# amp_soha_v2.net
KiCad netlist of a schematic drawn in EAGLE
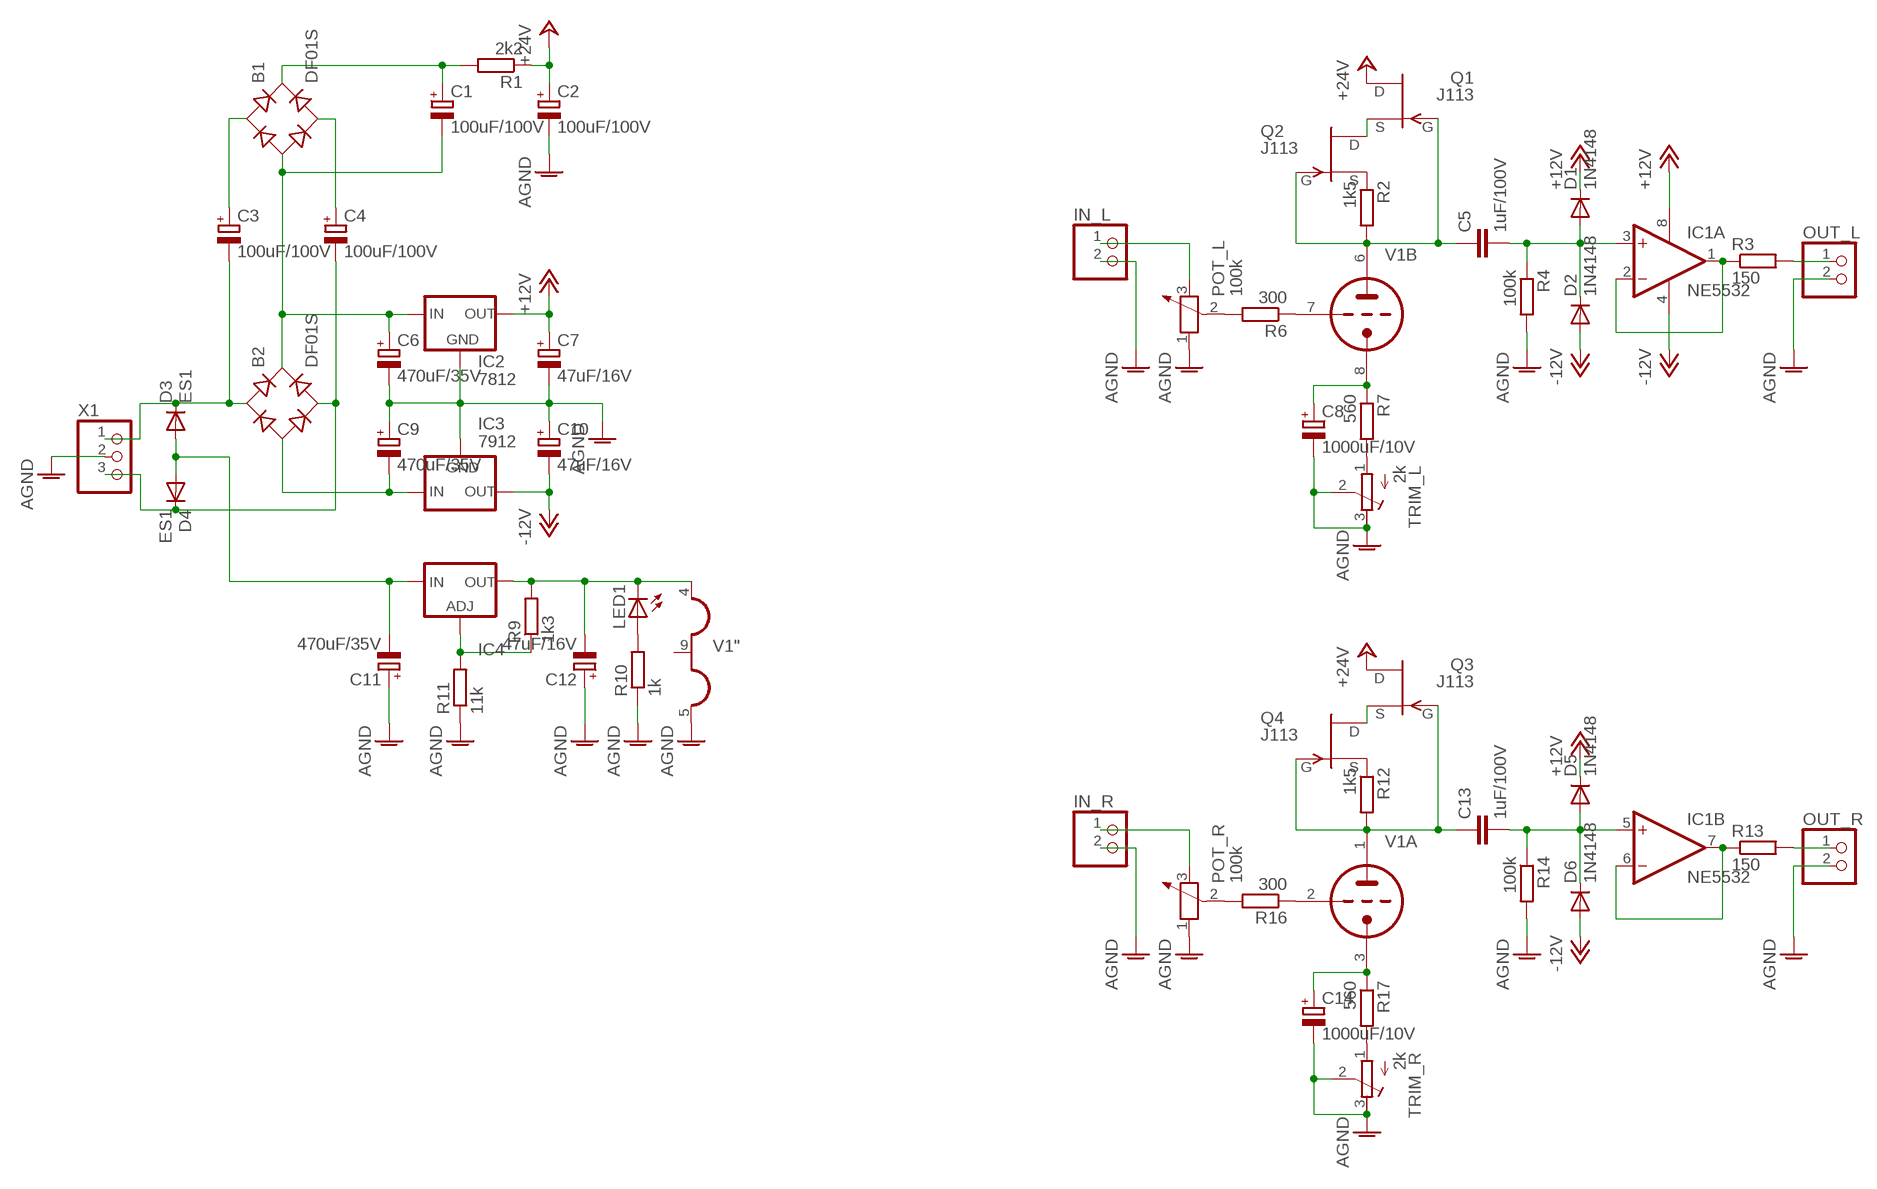
[diagram p0: schematic, sheet 1]

(export (version "E")
  (design (tool "Eeschema 10.0.6"))
  (components
    (comp (ref "B1")
      (value "DF01S")
      (footprint "eagle-import:DFS")
      (libsource (lib "eagle-import") (part "DFS01"))
    )
    (comp (ref "B2")
      (value "DF01S")
      (footprint "eagle-import:DFS")
      (libsource (lib "eagle-import") (part "DFS01"))
    )
    (comp (ref "C1")
      (value "100uF/100V")
      (footprint "eagle-import:E5-10,5")
      (libsource (lib "eagle-import") (part "CPOL-EUE5-10,5"))
    )
    (comp (ref "C2")
      (value "100uF/100V")
      (footprint "eagle-import:E5-10,5")
      (libsource (lib "eagle-import") (part "CPOL-EUE5-10,5"))
    )
    (comp (ref "C3")
      (value "100uF/100V")
      (footprint "eagle-import:E5-10,5")
      (libsource (lib "eagle-import") (part "CPOL-EUE5-10,5"))
    )
    (comp (ref "C4")
      (value "100uF/100V")
      (footprint "eagle-import:E5-10,5")
      (libsource (lib "eagle-import") (part "CPOL-EUE5-10,5"))
    )
    (comp (ref "C5")
      (value "1uF/100V")
      (footprint "eagle-import:C075-052X106")
      (libsource (lib "eagle-import") (part "C-EU075-052X106"))
    )
    (comp (ref "C6")
      (value "470uF/35V")
      (footprint "eagle-import:E5-10,5")
      (libsource (lib "eagle-import") (part "CPOL-EUE5-10,5"))
    )
    (comp (ref "C7")
      (value "47uF/16V")
      (footprint "eagle-import:E2,5-6")
      (libsource (lib "eagle-import") (part "CPOL-EUE2.5-6"))
    )
    (comp (ref "C8")
      (value "1000uF/10V")
      (footprint "eagle-import:E5-10,5")
      (libsource (lib "eagle-import") (part "CPOL-EUE5-10,5"))
    )
    (comp (ref "C9")
      (value "470uF/35V")
      (footprint "eagle-import:E5-10,5")
      (libsource (lib "eagle-import") (part "CPOL-EUE5-10,5"))
    )
    (comp (ref "C10")
      (value "47uF/16V")
      (footprint "eagle-import:E2,5-6")
      (libsource (lib "eagle-import") (part "CPOL-EUE2.5-6"))
    )
    (comp (ref "C11")
      (value "470uF/35V")
      (footprint "eagle-import:E5-10,5")
      (libsource (lib "eagle-import") (part "CPOL-EUE5-10,5"))
    )
    (comp (ref "C12")
      (value "47uF/16V")
      (footprint "eagle-import:E2,5-6")
      (libsource (lib "eagle-import") (part "CPOL-EUE2.5-6"))
    )
    (comp (ref "C13")
      (value "1uF/100V")
      (footprint "eagle-import:C075-052X106")
      (libsource (lib "eagle-import") (part "C-EU075-052X106"))
    )
    (comp (ref "C14")
      (value "1000uF/10V")
      (footprint "eagle-import:E5-10,5")
      (libsource (lib "eagle-import") (part "CPOL-EUE5-10,5"))
    )
    (comp (ref "D1")
      (value "1N4148")
      (footprint "eagle-import:D0805")
      (libsource (lib "eagle-import") (part "1N4148"))
    )
    (comp (ref "D2")
      (value "1N4148")
      (footprint "eagle-import:D0805")
      (libsource (lib "eagle-import") (part "1N4148"))
    )
    (comp (ref "D3")
      (value "ES1")
      (footprint "eagle-import:DO-214AC")
      (libsource (lib "eagle-import") (part "ES1"))
    )
    (comp (ref "D4")
      (value "ES1")
      (footprint "eagle-import:DO-214AC")
      (libsource (lib "eagle-import") (part "ES1"))
    )
    (comp (ref "D5")
      (value "1N4148")
      (footprint "eagle-import:D0805")
      (libsource (lib "eagle-import") (part "1N4148"))
    )
    (comp (ref "D6")
      (value "1N4148")
      (footprint "eagle-import:D0805")
      (libsource (lib "eagle-import") (part "1N4148"))
    )
    (comp (ref "IC1")
      (value "NE5532")
      (footprint "eagle-import:SO08")
      (libsource (lib "eagle-import") (part "NE5535U"))
    )
    (comp (ref "IC2")
      (value "7812")
      (footprint "eagle-import:78XXS")
      (libsource (lib "eagle-import") (part "78XXTO-220"))
    )
    (comp (ref "IC3")
      (value "7912")
      (footprint "eagle-import:79XXS")
      (libsource (lib "eagle-import") (part "79XXTO-220"))
    )
    (comp (ref "IC4")
      (value "LM337TS")
      (footprint "eagle-import:337TS")
      (libsource (lib "eagle-import") (part "LM337TS"))
    )
    (comp (ref "IN_L")
      (value "PINHD-1X2")
      (footprint "eagle-import:1X02")
      (libsource (lib "eagle-import") (part "PINHD-1X2"))
    )
    (comp (ref "IN_R")
      (value "PINHD-1X2")
      (footprint "eagle-import:1X02")
      (libsource (lib "eagle-import") (part "PINHD-1X2"))
    )
    (comp (ref "LED1")
      (value "LED5MM")
      (footprint "eagle-import:LED5MM")
      (libsource (lib "eagle-import") (part "LED5MM"))
    )
    (comp (ref "OUT_L")
      (value "PINHD-1X2")
      (footprint "eagle-import:1X02")
      (libsource (lib "eagle-import") (part "PINHD-1X2"))
    )
    (comp (ref "OUT_R")
      (value "PINHD-1X2")
      (footprint "eagle-import:1X02")
      (libsource (lib "eagle-import") (part "PINHD-1X2"))
    )
    (comp (ref "POT_L")
      (value "100k")
      (footprint "eagle-import:1X03")
      (libsource (lib "eagle-import") (part "POTENTIOMETER_"))
    )
    (comp (ref "POT_R")
      (value "100k")
      (footprint "eagle-import:1X03")
      (libsource (lib "eagle-import") (part "POTENTIOMETER_"))
    )
    (comp (ref "Q1")
      (value "J113")
      (footprint "eagle-import:TO92")
      (libsource (lib "eagle-import") (part "J113"))
    )
    (comp (ref "Q2")
      (value "J113")
      (footprint "eagle-import:TO92")
      (libsource (lib "eagle-import") (part "J113"))
    )
    (comp (ref "Q3")
      (value "J113")
      (footprint "eagle-import:TO92")
      (libsource (lib "eagle-import") (part "J113"))
    )
    (comp (ref "Q4")
      (value "J113")
      (footprint "eagle-import:TO92")
      (libsource (lib "eagle-import") (part "J113"))
    )
    (comp (ref "R1")
      (value "2k2")
      (footprint "eagle-import:R0805")
      (libsource (lib "eagle-import") (part "R-EU_"))
    )
    (comp (ref "R2")
      (value "1k5")
      (footprint "eagle-import:R0805")
      (libsource (lib "eagle-import") (part "R-EU_"))
    )
    (comp (ref "R3")
      (value "150")
      (footprint "eagle-import:R0805")
      (libsource (lib "eagle-import") (part "R-EU_"))
    )
    (comp (ref "R4")
      (value "100k")
      (footprint "eagle-import:R0805")
      (libsource (lib "eagle-import") (part "R-EU_"))
    )
    (comp (ref "R6")
      (value "300")
      (footprint "eagle-import:R0805")
      (libsource (lib "eagle-import") (part "R-EU_"))
    )
    (comp (ref "R7")
      (value "560")
      (footprint "eagle-import:R0805")
      (libsource (lib "eagle-import") (part "R-EU_"))
    )
    (comp (ref "R9")
      (value "1k3")
      (footprint "eagle-import:R0805")
      (libsource (lib "eagle-import") (part "R-EU_"))
    )
    (comp (ref "R10")
      (value "1k")
      (footprint "eagle-import:R0805")
      (libsource (lib "eagle-import") (part "R-EU_"))
    )
    (comp (ref "R11")
      (value "11k")
      (footprint "eagle-import:R0805")
      (libsource (lib "eagle-import") (part "R-EU_"))
    )
    (comp (ref "R12")
      (value "1k5")
      (footprint "eagle-import:R0805")
      (libsource (lib "eagle-import") (part "R-EU_"))
    )
    (comp (ref "R13")
      (value "150")
      (footprint "eagle-import:R0805")
      (libsource (lib "eagle-import") (part "R-EU_"))
    )
    (comp (ref "R14")
      (value "100k")
      (footprint "eagle-import:R0805")
      (libsource (lib "eagle-import") (part "R-EU_"))
    )
    (comp (ref "R16")
      (value "300")
      (footprint "eagle-import:R0805")
      (libsource (lib "eagle-import") (part "R-EU_"))
    )
    (comp (ref "R17")
      (value "560")
      (footprint "eagle-import:R0805")
      (libsource (lib "eagle-import") (part "R-EU_"))
    )
    (comp (ref "TRIM_L")
      (value "2k")
      (footprint "eagle-import:RTRIM3296W")
      (libsource (lib "eagle-import") (part "RTRIM329W"))
    )
    (comp (ref "TRIM_R")
      (value "2k")
      (footprint "eagle-import:RTRIM3296W")
      (libsource (lib "eagle-import") (part "RTRIM329W"))
    )
    (comp (ref "V1")
      (value "12AU7-P")
      (footprint "eagle-import:NOVAL")
      (libsource (lib "eagle-import") (part "12AU7-P"))
    )
    (comp (ref "X1")
      (value "W237-103")
      (footprint "eagle-import:W237-103")
      (libsource (lib "eagle-import") (part "W237-103"))
    )
  )
  (nets
    (net (code "1") (name "+12V") (class "Default")
      (node (ref "C7") (pin "+") (pinfunction "+_+") (pintype "passive"))
      (node (ref "D1") (pin "K") (pinfunction "C_K") (pintype "passive"))
      (node (ref "D5") (pin "K") (pinfunction "C_K") (pintype "passive"))
      (node (ref "IC1") (pin "8") (pinfunction "V+_8") (pintype "power_in"))
      (node (ref "IC2") (pin "OUT") (pinfunction "OUT_OUT") (pintype "passive"))
    )
    (net (code "2") (name "+24V") (class "Default")
      (node (ref "C2") (pin "+") (pinfunction "+_+") (pintype "passive"))
      (node (ref "Q1") (pin "3") (pinfunction "D_3") (pintype "passive"))
      (node (ref "Q3") (pin "3") (pinfunction "D_3") (pintype "passive"))
      (node (ref "R1") (pin "1") (pinfunction "1_1") (pintype "passive"))
    )
    (net (code "3") (name "-12V") (class "Default")
      (node (ref "C10") (pin "-") (pinfunction "-_-") (pintype "passive"))
      (node (ref "D2") (pin "A") (pinfunction "A_A") (pintype "passive"))
      (node (ref "D6") (pin "A") (pinfunction "A_A") (pintype "passive"))
      (node (ref "IC1") (pin "4") (pinfunction "V-_4") (pintype "power_in"))
      (node (ref "IC3") (pin "OUT") (pinfunction "OUT_OUT") (pintype "passive"))
    )
    (net (code "4") (name "AGND") (class "Default")
      (node (ref "C10") (pin "+") (pinfunction "+_+") (pintype "passive"))
      (node (ref "C11") (pin "+") (pinfunction "+_+") (pintype "passive"))
      (node (ref "C12") (pin "+") (pinfunction "+_+") (pintype "passive"))
      (node (ref "C14") (pin "-") (pinfunction "-_-") (pintype "passive"))
      (node (ref "C2") (pin "-") (pinfunction "-_-") (pintype "passive"))
      (node (ref "C6") (pin "-") (pinfunction "-_-") (pintype "passive"))
      (node (ref "C7") (pin "-") (pinfunction "-_-") (pintype "passive"))
      (node (ref "C8") (pin "-") (pinfunction "-_-") (pintype "passive"))
      (node (ref "C9") (pin "+") (pinfunction "+_+") (pintype "passive"))
      (node (ref "IC2") (pin "GND") (pinfunction "GND_GND") (pintype "input"))
      (node (ref "IC3") (pin "GND") (pinfunction "GND_GND") (pintype "input"))
      (node (ref "IN_L") (pin "2") (pinfunction "2_2") (pintype "passive"))
      (node (ref "IN_R") (pin "2") (pinfunction "2_2") (pintype "passive"))
      (node (ref "OUT_L") (pin "2") (pinfunction "2_2") (pintype "passive"))
      (node (ref "OUT_R") (pin "2") (pinfunction "2_2") (pintype "passive"))
      (node (ref "POT_L") (pin "1") (pinfunction "1_1") (pintype "passive"))
      (node (ref "POT_R") (pin "1") (pinfunction "1_1") (pintype "passive"))
      (node (ref "R10") (pin "1") (pinfunction "1_1") (pintype "passive"))
      (node (ref "R11") (pin "1") (pinfunction "1_1") (pintype "passive"))
      (node (ref "R14") (pin "2") (pinfunction "2_2") (pintype "passive"))
      (node (ref "R4") (pin "2") (pinfunction "2_2") (pintype "passive"))
      (node (ref "TRIM_L") (pin "2") (pinfunction "S_2") (pintype "passive"))
      (node (ref "TRIM_L") (pin "3") (pinfunction "E_3") (pintype "passive"))
      (node (ref "TRIM_R") (pin "2") (pinfunction "S_2") (pintype "passive"))
      (node (ref "TRIM_R") (pin "3") (pinfunction "E_3") (pintype "passive"))
      (node (ref "V1") (pin "5") (pinfunction "H3_5") (pintype "passive"))
      (node (ref "X1") (pin "2") (pinfunction "2_2") (pintype "passive"))
    )
    (net (code "5") (name "Net-(B1-Pad+)") (class "Default")
      (node (ref "B1") (pin "+") (pinfunction "+_+") (pintype "passive"))
      (node (ref "C1") (pin "+") (pinfunction "+_+") (pintype "passive"))
      (node (ref "R1") (pin "2") (pinfunction "2_2") (pintype "passive"))
    )
    (net (code "6") (name "Net-(B1-Pad-)") (class "Default")
      (node (ref "B1") (pin "-") (pinfunction "-_-") (pintype "passive"))
      (node (ref "B2") (pin "+") (pinfunction "+_+") (pintype "passive"))
      (node (ref "C1") (pin "-") (pinfunction "-_-") (pintype "passive"))
      (node (ref "C6") (pin "+") (pinfunction "+_+") (pintype "passive"))
      (node (ref "IC2") (pin "IN") (pinfunction "IN_IN") (pintype "input"))
    )
    (net (code "7") (name "Net-(B1-PadAC1)") (class "Default")
      (node (ref "B1") (pin "AC1") (pinfunction "AC1_AC1") (pintype "passive"))
      (node (ref "C3") (pin "+") (pinfunction "+_+") (pintype "passive"))
    )
    (net (code "8") (name "Net-(B1-PadAC2)") (class "Default")
      (node (ref "B1") (pin "AC2") (pinfunction "AC2_AC2") (pintype "passive"))
      (node (ref "C4") (pin "+") (pinfunction "+_+") (pintype "passive"))
    )
    (net (code "9") (name "Net-(B2-Pad-)") (class "Default")
      (node (ref "B2") (pin "-") (pinfunction "-_-") (pintype "passive"))
      (node (ref "C9") (pin "-") (pinfunction "-_-") (pintype "passive"))
      (node (ref "IC3") (pin "IN") (pinfunction "IN_IN") (pintype "input"))
    )
    (net (code "10") (name "Net-(B2-PadAC1)") (class "Default")
      (node (ref "B2") (pin "AC1") (pinfunction "AC1_AC1") (pintype "passive"))
      (node (ref "C3") (pin "-") (pinfunction "-_-") (pintype "passive"))
      (node (ref "D3") (pin "C") (pinfunction "C_C") (pintype "passive"))
      (node (ref "X1") (pin "1") (pinfunction "1_1") (pintype "passive"))
    )
    (net (code "11") (name "Net-(B2-PadAC2)") (class "Default")
      (node (ref "B2") (pin "AC2") (pinfunction "AC2_AC2") (pintype "passive"))
      (node (ref "C4") (pin "-") (pinfunction "-_-") (pintype "passive"))
      (node (ref "D4") (pin "C") (pinfunction "C_C") (pintype "passive"))
      (node (ref "X1") (pin "3") (pinfunction "3_3") (pintype "passive"))
    )
    (net (code "12") (name "Net-(D2-C)") (class "Default")
      (node (ref "C5") (pin "2") (pinfunction "2_2") (pintype "passive"))
      (node (ref "D1") (pin "A") (pinfunction "A_A") (pintype "passive"))
      (node (ref "D2") (pin "K") (pinfunction "C_K") (pintype "passive"))
      (node (ref "IC1") (pin "3") (pinfunction "+IN_3") (pintype "input"))
      (node (ref "R4") (pin "1") (pinfunction "1_1") (pintype "passive"))
    )
    (net (code "13") (name "Net-(D6-C)") (class "Default")
      (node (ref "C13") (pin "2") (pinfunction "2_2") (pintype "passive"))
      (node (ref "D5") (pin "A") (pinfunction "A_A") (pintype "passive"))
      (node (ref "D6") (pin "K") (pinfunction "C_K") (pintype "passive"))
      (node (ref "IC1") (pin "5") (pinfunction "+IN_5") (pintype "input"))
      (node (ref "R14") (pin "1") (pinfunction "1_1") (pintype "passive"))
    )
    (net (code "14") (name "Net-(IC1A--IN)") (class "Default")
      (node (ref "IC1") (pin "1") (pinfunction "OUT_1") (pintype "output"))
      (node (ref "IC1") (pin "2") (pinfunction "-IN_2") (pintype "input"))
      (node (ref "R3") (pin "1") (pinfunction "1_1") (pintype "passive"))
    )
    (net (code "15") (name "Net-(IC1B--IN)") (class "Default")
      (node (ref "IC1") (pin "6") (pinfunction "-IN_6") (pintype "input"))
      (node (ref "IC1") (pin "7") (pinfunction "OUT_7") (pintype "output"))
      (node (ref "R13") (pin "1") (pinfunction "1_1") (pintype "passive"))
    )
    (net (code "16") (name "Net-(IC4-ADJ)") (class "Default")
      (node (ref "IC4") (pin "1") (pinfunction "ADJ_1") (pintype "input"))
      (node (ref "R11") (pin "2") (pinfunction "2_2") (pintype "passive"))
      (node (ref "R9") (pin "1") (pinfunction "1_1") (pintype "passive"))
    )
    (net (code "17") (name "Net-(IC4-IN)") (class "Default")
      (node (ref "C11") (pin "-") (pinfunction "-_-") (pintype "passive"))
      (node (ref "D3") (pin "A") (pinfunction "A_A") (pintype "passive"))
      (node (ref "D4") (pin "A") (pinfunction "A_A") (pintype "passive"))
      (node (ref "IC4") (pin "2") (pinfunction "IN_2") (pintype "input"))
    )
    (net (code "18") (name "Net-(IC4-OUT)") (class "Default")
      (node (ref "C12") (pin "-") (pinfunction "-_-") (pintype "passive"))
      (node (ref "IC4") (pin "3") (pinfunction "OUT_3") (pintype "passive"))
      (node (ref "LED1") (pin "K") (pinfunction "C_K") (pintype "passive"))
      (node (ref "R9") (pin "2") (pinfunction "2_2") (pintype "passive"))
      (node (ref "V1") (pin "4") (pinfunction "H1_4") (pintype "passive"))
    )
    (net (code "19") (name "Net-(LED1-PadA)") (class "Default")
      (node (ref "LED1") (pin "A") (pinfunction "A_A") (pintype "passive"))
      (node (ref "R10") (pin "2") (pinfunction "2_2") (pintype "passive"))
    )
    (net (code "20") (name "Net-(OUT_L-Pad1)") (class "Default")
      (node (ref "OUT_L") (pin "1") (pinfunction "1_1") (pintype "passive"))
      (node (ref "R3") (pin "2") (pinfunction "2_2") (pintype "passive"))
    )
    (net (code "21") (name "Net-(OUT_R-Pad1)") (class "Default")
      (node (ref "OUT_R") (pin "1") (pinfunction "1_1") (pintype "passive"))
      (node (ref "R13") (pin "2") (pinfunction "2_2") (pintype "passive"))
    )
    (net (code "22") (name "Net-(POT_L-2)") (class "Default")
      (node (ref "IN_L") (pin "1") (pinfunction "1_1") (pintype "passive"))
      (node (ref "POT_L") (pin "3") (pinfunction "2_3") (pintype "passive"))
    )
    (net (code "23") (name "Net-(POT_L-3)") (class "Default")
      (node (ref "POT_L") (pin "2") (pinfunction "3_2") (pintype "passive"))
      (node (ref "R6") (pin "2") (pinfunction "2_2") (pintype "passive"))
    )
    (net (code "24") (name "Net-(POT_R-2)") (class "Default")
      (node (ref "IN_R") (pin "1") (pinfunction "1_1") (pintype "passive"))
      (node (ref "POT_R") (pin "3") (pinfunction "2_3") (pintype "passive"))
    )
    (net (code "25") (name "Net-(POT_R-3)") (class "Default")
      (node (ref "POT_R") (pin "2") (pinfunction "3_2") (pintype "passive"))
      (node (ref "R16") (pin "2") (pinfunction "2_2") (pintype "passive"))
    )
    (net (code "26") (name "Net-(Q1-G)") (class "Default")
      (node (ref "C5") (pin "1") (pinfunction "1_1") (pintype "passive"))
      (node (ref "Q1") (pin "1") (pinfunction "G_1") (pintype "passive"))
      (node (ref "Q2") (pin "1") (pinfunction "G_1") (pintype "passive"))
      (node (ref "R2") (pin "2") (pinfunction "2_2") (pintype "passive"))
      (node (ref "V1") (pin "6") (pinfunction "TA_6") (pintype "passive"))
    )
    (net (code "27") (name "Net-(Q1-S)") (class "Default")
      (node (ref "Q1") (pin "2") (pinfunction "S_2") (pintype "passive"))
      (node (ref "Q2") (pin "3") (pinfunction "D_3") (pintype "passive"))
    )
    (net (code "28") (name "Net-(Q2-S)") (class "Default")
      (node (ref "Q2") (pin "2") (pinfunction "S_2") (pintype "passive"))
      (node (ref "R2") (pin "1") (pinfunction "1_1") (pintype "passive"))
    )
    (net (code "29") (name "Net-(Q3-G)") (class "Default")
      (node (ref "C13") (pin "1") (pinfunction "1_1") (pintype "passive"))
      (node (ref "Q3") (pin "1") (pinfunction "G_1") (pintype "passive"))
      (node (ref "Q4") (pin "1") (pinfunction "G_1") (pintype "passive"))
      (node (ref "R12") (pin "2") (pinfunction "2_2") (pintype "passive"))
      (node (ref "V1") (pin "1") (pinfunction "TA_1") (pintype "passive"))
    )
    (net (code "30") (name "Net-(Q3-S)") (class "Default")
      (node (ref "Q3") (pin "2") (pinfunction "S_2") (pintype "passive"))
      (node (ref "Q4") (pin "3") (pinfunction "D_3") (pintype "passive"))
    )
    (net (code "31") (name "Net-(Q4-S)") (class "Default")
      (node (ref "Q4") (pin "2") (pinfunction "S_2") (pintype "passive"))
      (node (ref "R12") (pin "1") (pinfunction "1_1") (pintype "passive"))
    )
    (net (code "32") (name "Net-(TRIM_L-A)") (class "Default")
      (node (ref "R7") (pin "2") (pinfunction "2_2") (pintype "passive"))
      (node (ref "TRIM_L") (pin "1") (pinfunction "A_1") (pintype "passive"))
    )
    (net (code "33") (name "Net-(TRIM_R-A)") (class "Default")
      (node (ref "R17") (pin "2") (pinfunction "2_2") (pintype "passive"))
      (node (ref "TRIM_R") (pin "1") (pinfunction "A_1") (pintype "passive"))
    )
    (net (code "34") (name "Net-(V1B-TG)") (class "Default")
      (node (ref "R16") (pin "1") (pinfunction "1_1") (pintype "passive"))
      (node (ref "V1") (pin "2") (pinfunction "TG_2") (pintype "passive"))
    )
    (net (code "35") (name "Net-(V1B-TK)") (class "Default")
      (node (ref "C14") (pin "+") (pinfunction "+_+") (pintype "passive"))
      (node (ref "R17") (pin "1") (pinfunction "1_1") (pintype "passive"))
      (node (ref "V1") (pin "3") (pinfunction "TK_3") (pintype "passive"))
    )
    (net (code "36") (name "Net-(V1C-TG)") (class "Default")
      (node (ref "R6") (pin "1") (pinfunction "1_1") (pintype "passive"))
      (node (ref "V1") (pin "7") (pinfunction "TG_7") (pintype "passive"))
    )
    (net (code "37") (name "Net-(V1C-TK)") (class "Default")
      (node (ref "C8") (pin "+") (pinfunction "+_+") (pintype "passive"))
      (node (ref "R7") (pin "1") (pinfunction "1_1") (pintype "passive"))
      (node (ref "V1") (pin "8") (pinfunction "TK_8") (pintype "passive"))
    )
    (net (code "38") (name "unconnected-(V1A-H2-Pad9)") (class "Default")
      (node (ref "V1") (pin "9") (pinfunction "H2_9") (pintype "passive"))
    )
  )
)
